# Sheet1.net
KiCad netlist of a schematic drawn in Altium Designer
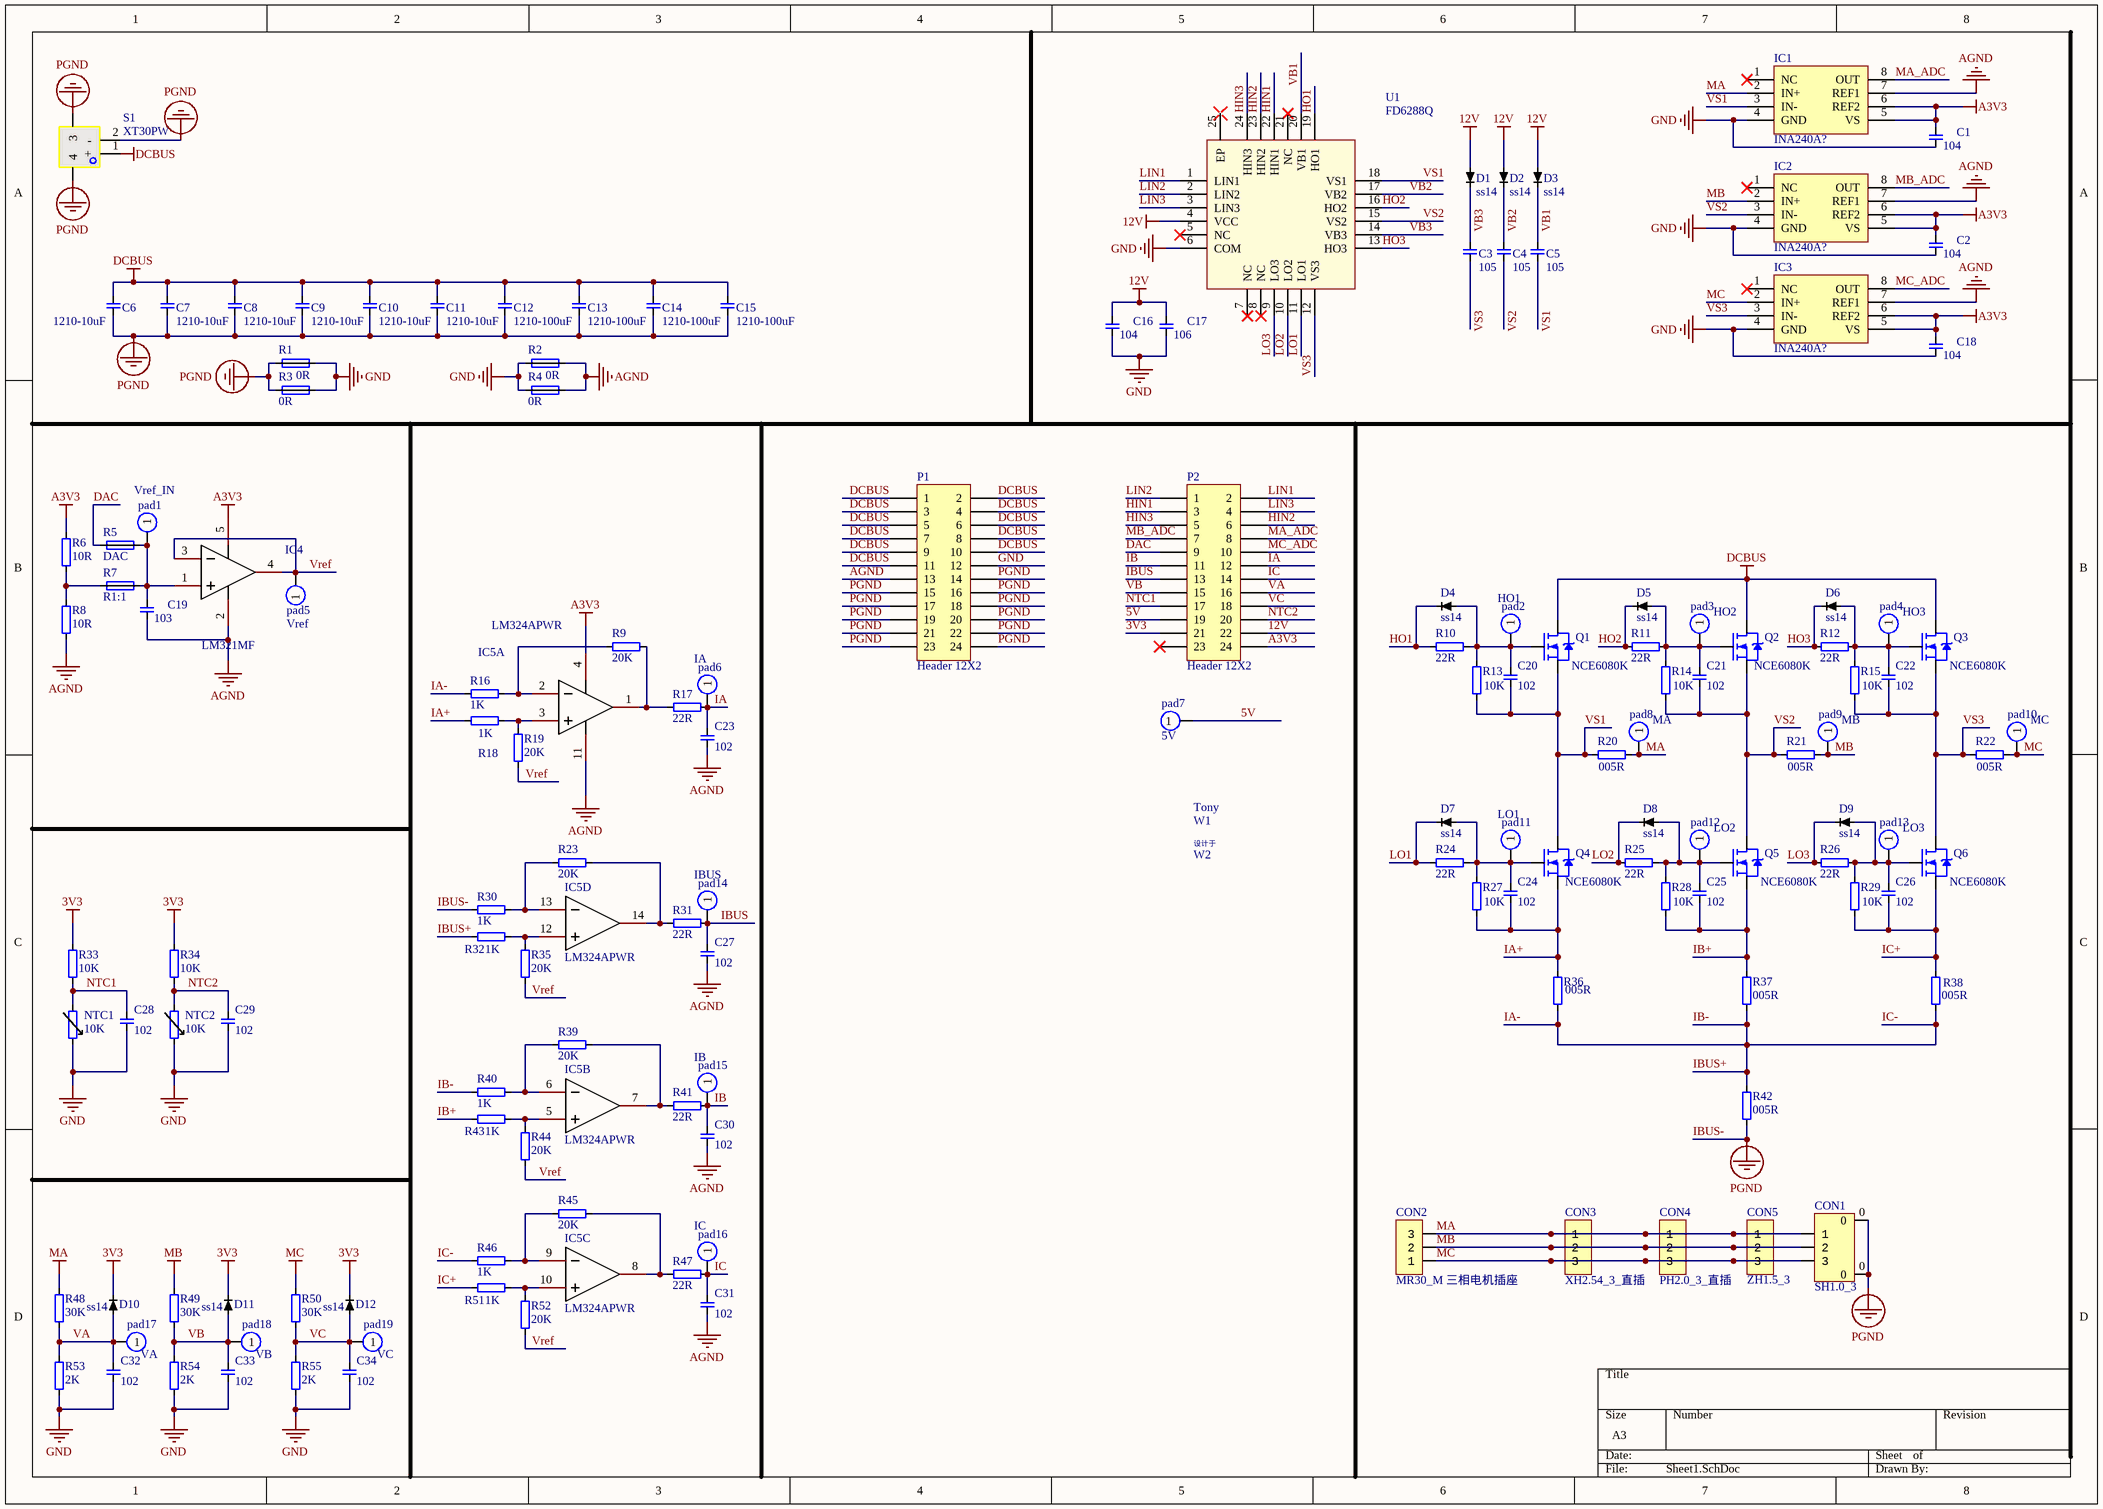
[diagram p0: Sheet1.SchDoc]

(export (version "E")
  (design (tool "Eeschema 10.0.6"))
  (components
    (comp (ref "C1") (value "104") (footprint "CAP_0603") (libsource (lib "基本元件库") (part "cap")))
    (comp (ref "C2") (value "104") (footprint "CAP_0603") (libsource (lib "基本元件库") (part "cap")))
    (comp (ref "C3") (value "105") (footprint "CAP_0603") (libsource (lib "基本元件库") (part "cap")))
    (comp (ref "C4") (value "105") (footprint "CAP_0603") (libsource (lib "基本元件库") (part "cap")))
    (comp (ref "C5") (value "105") (footprint "CAP_0603") (libsource (lib "基本元件库") (part "cap")))
    (comp (ref "C6") (value "1210-10uF") (footprint "CAP_1210_L") (libsource (lib "基本元件库") (part "cap")))
    (comp (ref "C7") (value "1210-10uF") (footprint "CAP_1210_L") (libsource (lib "基本元件库") (part "cap")))
    (comp (ref "C8") (value "1210-10uF") (footprint "CAP_1210_L") (libsource (lib "基本元件库") (part "cap")))
    (comp (ref "C9") (value "1210-10uF") (footprint "CAP_1210_L") (libsource (lib "基本元件库") (part "cap")))
    (comp (ref "C10") (value "1210-10uF") (footprint "CAP_1210_L") (libsource (lib "基本元件库") (part "cap")))
    (comp (ref "C11") (value "1210-10uF") (footprint "CAP_1210_L") (libsource (lib "基本元件库") (part "cap")))
    (comp (ref "C12") (value "1210-100uF") (footprint "CAP_1210_L") (libsource (lib "基本元件库") (part "cap")))
    (comp (ref "C13") (value "1210-100uF") (footprint "CAP_1210_L") (libsource (lib "基本元件库") (part "cap")))
    (comp (ref "C14") (value "1210-100uF") (footprint "CAP_1210_L") (libsource (lib "基本元件库") (part "cap")))
    (comp (ref "C15") (value "1210-100uF") (footprint "CAP_1210_L") (libsource (lib "基本元件库") (part "cap")))
    (comp (ref "C16") (value "104") (footprint "CAP_0603") (libsource (lib "基本元件库") (part "cap")))
    (comp (ref "C17") (value "106") (footprint "CAP_0603") (libsource (lib "基本元件库") (part "cap")))
    (comp (ref "C18") (value "104") (footprint "CAP_0603") (libsource (lib "基本元件库") (part "cap")))
    (comp (ref "C19") (value "103") (footprint "CAP_0603") (libsource (lib "基本元件库") (part "cap")))
    (comp (ref "C20") (value "102") (footprint "CAP_0603") (libsource (lib "基本元件库") (part "cap")))
    (comp (ref "C21") (value "102") (footprint "CAP_0603") (libsource (lib "基本元件库") (part "cap")))
    (comp (ref "C22") (value "102") (footprint "CAP_0603") (libsource (lib "基本元件库") (part "cap")))
    (comp (ref "C23") (value "102") (footprint "CAP_0603") (libsource (lib "基本元件库") (part "cap")))
    (comp (ref "C24") (value "102") (footprint "CAP_0603") (libsource (lib "基本元件库") (part "cap")))
    (comp (ref "C25") (value "102") (footprint "CAP_0603") (libsource (lib "基本元件库") (part "cap")))
    (comp (ref "C26") (value "102") (footprint "CAP_0603") (libsource (lib "基本元件库") (part "cap")))
    (comp (ref "C27") (value "102") (footprint "CAP_0603") (libsource (lib "基本元件库") (part "cap")))
    (comp (ref "C28") (value "102") (footprint "CAP_0603") (libsource (lib "基本元件库") (part "cap")))
    (comp (ref "C29") (value "102") (footprint "CAP_0603") (libsource (lib "基本元件库") (part "cap")))
    (comp (ref "C30") (value "102") (footprint "CAP_0603") (libsource (lib "基本元件库") (part "cap")))
    (comp (ref "C31") (value "102") (footprint "CAP_0603") (libsource (lib "基本元件库") (part "cap")))
    (comp (ref "C32") (value "102") (footprint "CAP_0603") (libsource (lib "基本元件库") (part "cap")))
    (comp (ref "C33") (value "102") (footprint "CAP_0603") (libsource (lib "基本元件库") (part "cap")))
    (comp (ref "C34") (value "102") (footprint "CAP_0603") (libsource (lib "基本元件库") (part "cap")))
    (comp (ref "CON1")
      (value "SH1.0_3")
      (footprint "SH1.0 LS 3P")
      (description "SH1.0 座子")
      (libsource (lib "接插件库") (part "SH1.0_3"))
    )
    (comp (ref "CON2")
      (value "MR30_M 三相电机插座")
      (footprint "MR30-M")
      (description "三相电机线插座")
      (libsource (lib "接插件库") (part "MR30_M"))
    )
    (comp (ref "CON3")
      (value "XH2.54_3_直插")
      (footprint "XH2.54-LI-3P")
      (description "XH2.54_3 直插 座子")
      (libsource (lib "接插件库") (part "XH2.54_3_L"))
    )
    (comp (ref "CON4")
      (value "PH2.0_3_直插")
      (footprint "PH2.0-LI-3P")
      (description "PH2.0_3 直插 座子")
      (libsource (lib "接插件库") (part "PH2.0_3_L"))
    )
    (comp (ref "CON5")
      (value "ZH1.5_3")
      (footprint "ZH1.5-LI-3P")
      (description "ZH1.5_3 座子")
      (libsource (lib "接插件库") (part "ZH1.5_3_L"))
    )
    (comp (ref "D1") (value "ss14") (footprint "SOD-323") (libsource (lib "基本元件库") (part "Diode")))
    (comp (ref "D2") (value "ss14") (footprint "SOD-323") (libsource (lib "基本元件库") (part "Diode")))
    (comp (ref "D3") (value "ss14") (footprint "SOD-323") (libsource (lib "基本元件库") (part "Diode")))
    (comp (ref "D4") (value "ss14") (footprint "SOD-323") (libsource (lib "基本元件库") (part "Diode")))
    (comp (ref "D5") (value "ss14") (footprint "SOD-323") (libsource (lib "基本元件库") (part "Diode")))
    (comp (ref "D6") (value "ss14") (footprint "SOD-323") (libsource (lib "基本元件库") (part "Diode")))
    (comp (ref "D7") (value "ss14") (footprint "SOD-323") (libsource (lib "基本元件库") (part "Diode")))
    (comp (ref "D8") (value "ss14") (footprint "SOD-323") (libsource (lib "基本元件库") (part "Diode")))
    (comp (ref "D9") (value "ss14") (footprint "SOD-323") (libsource (lib "基本元件库") (part "Diode")))
    (comp (ref "D10") (value "ss14") (footprint "SOD-323") (libsource (lib "基本元件库") (part "Diode")))
    (comp (ref "D11") (value "ss14") (footprint "SOD-323") (libsource (lib "基本元件库") (part "Diode")))
    (comp (ref "D12") (value "ss14") (footprint "SOD-323") (libsource (lib "基本元件库") (part "Diode")))
    (comp (ref "IC1")
      (value "INA240A?")
      (footprint "TSSOP8")
      (description "电流采样芯片\r\nA1=20 A2=50 A3=100 A4=200")
      (libsource (lib "IC") (part "INA240"))
    )
    (comp (ref "IC2")
      (value "INA240A?")
      (footprint "TSSOP8")
      (description "电流采样芯片\r\nA1=20 A2=50 A3=100 A4=200")
      (libsource (lib "IC") (part "INA240"))
    )
    (comp (ref "IC3")
      (value "INA240A?")
      (footprint "TSSOP8")
      (description "电流采样芯片\r\nA1=20 A2=50 A3=100 A4=200")
      (libsource (lib "IC") (part "INA240"))
    )
    (comp (ref "IC4")
      (value "LM321MF")
      (footprint "SOT23-5")
      (description "单通道运放")
      (fields (field (name "MANUFACTURER") "TI(德州仪器)") (field (name "MANUFACTURER PART") "LM321MF/NOPB"))
      (libsource (lib "IC") (part "LM321MF"))
    )
    (comp (ref "IC5")
      (value "LM324APWR")
      (footprint "SOP14")
      (description "四通道运放")
      (fields
        (field (name "MANUFACTURER") "TL084CPWR")
        (field (name "MANUFACTURER PART") "TI")
        (field (name "NAME") "LM324APWR")
      )
      (libsource (lib "IC") (part "LM324APWR"))
    )
    (comp (ref "NTC1")
      (value "10K")
      (footprint "RES_0603")
      (description "温敏电阻")
      (libsource (lib "基本元件库") (part "NTC"))
    )
    (comp (ref "NTC2")
      (value "10K")
      (footprint "RES_0603")
      (description "温敏电阻")
      (libsource (lib "基本元件库") (part "NTC"))
    )
    (comp (ref "P1")
      (value "Header 12X2")
      (footprint "HDR2X12")
      (description "Header, 12-Pin, Dual row")
      (fields (field (name "PUBLISHER") "Altium Limited"))
      (libsource (lib "Miscellaneous Connectors") (part "Header 12X2"))
    )
    (comp (ref "P2")
      (value "Header 12X2")
      (footprint "HDR2X12")
      (description "Header, 12-Pin, Dual row")
      (fields (field (name "PUBLISHER") "Altium Limited"))
      (libsource (lib "Miscellaneous Connectors") (part "Header 12X2"))
    )
    (comp (ref "pad1")
      (value "Vref_IN")
      (footprint "PAD-1")
      (description "50mil单点焊盘，用于测试")
      (libsource (lib "基本元件库") (part "PAD"))
    )
    (comp (ref "pad2")
      (value "HO1")
      (footprint "PAD-1")
      (description "50mil单点焊盘，用于测试")
      (libsource (lib "基本元件库") (part "PAD"))
    )
    (comp (ref "pad3")
      (value "HO2")
      (footprint "PAD-1")
      (description "50mil单点焊盘，用于测试")
      (libsource (lib "基本元件库") (part "PAD"))
    )
    (comp (ref "pad4")
      (value "HO3")
      (footprint "PAD-1")
      (description "50mil单点焊盘，用于测试")
      (libsource (lib "基本元件库") (part "PAD"))
    )
    (comp (ref "pad5")
      (value "Vref")
      (footprint "PAD-1")
      (description "50mil单点焊盘，用于测试")
      (libsource (lib "基本元件库") (part "PAD"))
    )
    (comp (ref "pad6")
      (value "IA")
      (footprint "PAD-1")
      (description "50mil单点焊盘，用于测试")
      (libsource (lib "基本元件库") (part "PAD"))
    )
    (comp (ref "pad7")
      (value "5V")
      (footprint "PAD-1")
      (description "50mil单点焊盘，用于测试")
      (libsource (lib "基本元件库") (part "PAD"))
    )
    (comp (ref "pad8")
      (value "MA")
      (footprint "PAD-1")
      (description "50mil单点焊盘，用于测试")
      (libsource (lib "基本元件库") (part "PAD"))
    )
    (comp (ref "pad9")
      (value "MB")
      (footprint "PAD-1")
      (description "50mil单点焊盘，用于测试")
      (libsource (lib "基本元件库") (part "PAD"))
    )
    (comp (ref "pad10")
      (value "MC")
      (footprint "PAD-1")
      (description "50mil单点焊盘，用于测试")
      (libsource (lib "基本元件库") (part "PAD"))
    )
    (comp (ref "pad11")
      (value "LO1")
      (footprint "PAD-1")
      (description "50mil单点焊盘，用于测试")
      (libsource (lib "基本元件库") (part "PAD"))
    )
    (comp (ref "pad12")
      (value "LO2")
      (footprint "PAD-1")
      (description "50mil单点焊盘，用于测试")
      (libsource (lib "基本元件库") (part "PAD"))
    )
    (comp (ref "pad13")
      (value "LO3")
      (footprint "PAD-1")
      (description "50mil单点焊盘，用于测试")
      (libsource (lib "基本元件库") (part "PAD"))
    )
    (comp (ref "pad14")
      (value "IBUS")
      (footprint "PAD-1")
      (description "50mil单点焊盘，用于测试")
      (libsource (lib "基本元件库") (part "PAD"))
    )
    (comp (ref "pad15")
      (value "IB")
      (footprint "PAD-1")
      (description "50mil单点焊盘，用于测试")
      (libsource (lib "基本元件库") (part "PAD"))
    )
    (comp (ref "pad16")
      (value "IC")
      (footprint "PAD-1")
      (description "50mil单点焊盘，用于测试")
      (libsource (lib "基本元件库") (part "PAD"))
    )
    (comp (ref "pad17")
      (value "VA")
      (footprint "PAD-1")
      (description "50mil单点焊盘，用于测试")
      (libsource (lib "基本元件库") (part "PAD"))
    )
    (comp (ref "pad18")
      (value "VB")
      (footprint "PAD-1")
      (description "50mil单点焊盘，用于测试")
      (libsource (lib "基本元件库") (part "PAD"))
    )
    (comp (ref "pad19")
      (value "VC")
      (footprint "PAD-1")
      (description "50mil单点焊盘，用于测试")
      (libsource (lib "基本元件库") (part "PAD"))
    )
    (comp (ref "Q1")
      (value "NCE6080K")
      (footprint "TO252-2")
      (description "N沟道MOSFIT\r\n-NCE6080K-TO252-2")
      (libsource (lib "基本元件库") (part "NMOS"))
    )
    (comp (ref "Q2")
      (value "NCE6080K")
      (footprint "TO252-2")
      (description "N沟道MOSFIT\r\n-NCE6080K-TO252-2")
      (libsource (lib "基本元件库") (part "NMOS"))
    )
    (comp (ref "Q3")
      (value "NCE6080K")
      (footprint "TO252-2")
      (description "N沟道MOSFIT\r\n-NCE6080K-TO252-2")
      (libsource (lib "基本元件库") (part "NMOS"))
    )
    (comp (ref "Q4")
      (value "NCE6080K")
      (footprint "TO252-2")
      (description "N沟道MOSFIT\r\n-NCE6080K-TO252-2")
      (libsource (lib "基本元件库") (part "NMOS"))
    )
    (comp (ref "Q5")
      (value "NCE6080K")
      (footprint "TO252-2")
      (description "N沟道MOSFIT\r\n-NCE6080K-TO252-2")
      (libsource (lib "基本元件库") (part "NMOS"))
    )
    (comp (ref "Q6")
      (value "NCE6080K")
      (footprint "TO252-2")
      (description "N沟道MOSFIT\r\n-NCE6080K-TO252-2")
      (libsource (lib "基本元件库") (part "NMOS"))
    )
    (comp (ref "R1") (value "0R") (footprint "RES_0805-SHORT") (libsource (lib "基本元件库") (part "Res-SHORT")))
    (comp (ref "R2") (value "0R") (footprint "RES_0805-SHORT") (libsource (lib "基本元件库") (part "Res-SHORT")))
    (comp (ref "R3") (value "0R") (footprint "RES_0805-SHORT") (libsource (lib "基本元件库") (part "Res-SHORT")))
    (comp (ref "R4") (value "0R") (footprint "RES_0805-SHORT") (libsource (lib "基本元件库") (part "Res-SHORT")))
    (comp (ref "R5") (value "DAC") (footprint "RES_0603-SHORT") (libsource (lib "基本元件库") (part "Res-SHORT")))
    (comp (ref "R6") (value "10R") (footprint "RES_0603") (libsource (lib "基本元件库") (part "Res")))
    (comp (ref "R7") (value "R1:1") (footprint "RES_0603-SHORT") (libsource (lib "基本元件库") (part "Res-SHORT")))
    (comp (ref "R8") (value "10R") (footprint "RES_0603") (libsource (lib "基本元件库") (part "Res")))
    (comp (ref "R9") (value "20K") (footprint "RES_0603") (libsource (lib "基本元件库") (part "Res")))
    (comp (ref "R10") (value "22R") (footprint "RES_0603") (libsource (lib "基本元件库") (part "Res")))
    (comp (ref "R11") (value "22R") (footprint "RES_0603") (libsource (lib "基本元件库") (part "Res")))
    (comp (ref "R12") (value "22R") (footprint "RES_0603") (libsource (lib "基本元件库") (part "Res")))
    (comp (ref "R13") (value "10K") (footprint "RES_0603") (libsource (lib "基本元件库") (part "Res")))
    (comp (ref "R14") (value "10K") (footprint "RES_0603") (libsource (lib "基本元件库") (part "Res")))
    (comp (ref "R15") (value "10K") (footprint "RES_0603") (libsource (lib "基本元件库") (part "Res")))
    (comp (ref "R16") (value "1K") (footprint "RES_0603") (libsource (lib "基本元件库") (part "Res")))
    (comp (ref "R17") (value "22R") (footprint "RES_0603") (libsource (lib "基本元件库") (part "Res")))
    (comp (ref "R18") (value "1K") (footprint "RES_0603") (libsource (lib "基本元件库") (part "Res")))
    (comp (ref "R19") (value "20K") (footprint "RES_0603") (libsource (lib "基本元件库") (part "Res")))
    (comp (ref "R20") (value "005R") (footprint "RES_2512") (libsource (lib "基本元件库") (part "Res")))
    (comp (ref "R21") (value "005R") (footprint "RES_2512") (libsource (lib "基本元件库") (part "Res")))
    (comp (ref "R22") (value "005R") (footprint "RES_2512") (libsource (lib "基本元件库") (part "Res")))
    (comp (ref "R23") (value "20K") (footprint "RES_0603") (libsource (lib "基本元件库") (part "Res")))
    (comp (ref "R24") (value "22R") (footprint "RES_0603") (libsource (lib "基本元件库") (part "Res")))
    (comp (ref "R25") (value "22R") (footprint "RES_0603") (libsource (lib "基本元件库") (part "Res")))
    (comp (ref "R26") (value "22R") (footprint "RES_0603") (libsource (lib "基本元件库") (part "Res")))
    (comp (ref "R27") (value "10K") (footprint "RES_0603") (libsource (lib "基本元件库") (part "Res")))
    (comp (ref "R28") (value "10K") (footprint "RES_0603") (libsource (lib "基本元件库") (part "Res")))
    (comp (ref "R29") (value "10K") (footprint "RES_0603") (libsource (lib "基本元件库") (part "Res")))
    (comp (ref "R30") (value "1K") (footprint "RES_0603") (libsource (lib "基本元件库") (part "Res")))
    (comp (ref "R31") (value "22R") (footprint "RES_0603") (libsource (lib "基本元件库") (part "Res")))
    (comp (ref "R32") (value "1K") (footprint "RES_0603") (libsource (lib "基本元件库") (part "Res")))
    (comp (ref "R33") (value "10K") (footprint "RES_0603") (libsource (lib "基本元件库") (part "Res")))
    (comp (ref "R34") (value "10K") (footprint "RES_0603") (libsource (lib "基本元件库") (part "Res")))
    (comp (ref "R35") (value "20K") (footprint "RES_0603") (libsource (lib "基本元件库") (part "Res")))
    (comp (ref "R36") (value "005R") (footprint "RES_2512") (libsource (lib "基本元件库") (part "Res")))
    (comp (ref "R37") (value "005R") (footprint "RES_2512") (libsource (lib "基本元件库") (part "Res")))
    (comp (ref "R38") (value "005R") (footprint "RES_2512") (libsource (lib "基本元件库") (part "Res")))
    (comp (ref "R39") (value "20K") (footprint "RES_0603") (libsource (lib "基本元件库") (part "Res")))
    (comp (ref "R40") (value "1K") (footprint "RES_0603") (libsource (lib "基本元件库") (part "Res")))
    (comp (ref "R41") (value "22R") (footprint "RES_0603") (libsource (lib "基本元件库") (part "Res")))
    (comp (ref "R42") (value "005R") (footprint "RES_2512") (libsource (lib "基本元件库") (part "Res")))
    (comp (ref "R43") (value "1K") (footprint "RES_0603") (libsource (lib "基本元件库") (part "Res")))
    (comp (ref "R44") (value "20K") (footprint "RES_0603") (libsource (lib "基本元件库") (part "Res")))
    (comp (ref "R45") (value "20K") (footprint "RES_0603") (libsource (lib "基本元件库") (part "Res")))
    (comp (ref "R46") (value "1K") (footprint "RES_0603") (libsource (lib "基本元件库") (part "Res")))
    (comp (ref "R47") (value "22R") (footprint "RES_0603") (libsource (lib "基本元件库") (part "Res")))
    (comp (ref "R48") (value "30K") (footprint "RES_0603") (libsource (lib "基本元件库") (part "Res")))
    (comp (ref "R49") (value "30K") (footprint "RES_0603") (libsource (lib "基本元件库") (part "Res")))
    (comp (ref "R50") (value "30K") (footprint "RES_0603") (libsource (lib "基本元件库") (part "Res")))
    (comp (ref "R51") (value "1K") (footprint "RES_0603") (libsource (lib "基本元件库") (part "Res")))
    (comp (ref "R52") (value "20K") (footprint "RES_0603") (libsource (lib "基本元件库") (part "Res")))
    (comp (ref "R53") (value "2K") (footprint "RES_0603") (libsource (lib "基本元件库") (part "Res")))
    (comp (ref "R54") (value "2K") (footprint "RES_0603") (libsource (lib "基本元件库") (part "Res")))
    (comp (ref "R55") (value "2K") (footprint "RES_0603") (libsource (lib "基本元件库") (part "Res")))
    (comp (ref "S1")
      (value "XT30PW")
      (footprint "XT30PW-M")
      (description "XT30PW-I/O")
      (libsource (lib "SOURCE") (part "XT30PW"))
    )
    (comp (ref "U1")
      (value "FD6288Q")
      (footprint "QFN-24_4X4")
      (description "栅极驱动IC")
      (libsource (lib "IC") (part "FD6288Q"))
    )
    (comp (ref "W1") (value "Tony") (footprint "Tony_2(200-70)") (libsource (lib "丝印库") (part "Tony")))
    (comp (ref "W2") (value "设计于") (footprint "designed by（430-70）") (libsource (lib "丝印库") (part "设计于")))
  )
  (nets
    (net (code "1") (name "/5V") (class "Default")
      (node (ref "P2") (pin "19") (pinfunction "19_19") (pintype "passive"))
      (node (ref "pad7") (pin "1") (pinfunction "1_1") (pintype "passive"))
    )
    (net (code "2") (name "/DAC") (class "Default")
      (node (ref "P2") (pin "9") (pinfunction "9_9") (pintype "passive"))
      (node (ref "R5") (pin "1") (pinfunction "1_1") (pintype "passive"))
    )
    (net (code "3") (name "/HIN1") (class "Default")
      (node (ref "P2") (pin "3") (pinfunction "3_3") (pintype "passive"))
      (node (ref "U1") (pin "22") (pinfunction "HIN1_22") (pintype "passive"))
    )
    (net (code "4") (name "/HIN2") (class "Default")
      (node (ref "P2") (pin "6") (pinfunction "6_6") (pintype "passive"))
      (node (ref "U1") (pin "23") (pinfunction "HIN2_23") (pintype "passive"))
    )
    (net (code "5") (name "/HIN3") (class "Default")
      (node (ref "P2") (pin "5") (pinfunction "5_5") (pintype "passive"))
      (node (ref "U1") (pin "24") (pinfunction "HIN3_24") (pintype "passive"))
    )
    (net (code "6") (name "/HO1") (class "Default")
      (node (ref "D4") (pin "2") (pintype "passive"))
      (node (ref "R10") (pin "2") (pinfunction "2_2") (pintype "passive"))
      (node (ref "U1") (pin "19") (pinfunction "HO1_19") (pintype "passive"))
    )
    (net (code "7") (name "/HO2") (class "Default")
      (node (ref "D5") (pin "2") (pintype "passive"))
      (node (ref "R11") (pin "2") (pinfunction "2_2") (pintype "passive"))
      (node (ref "U1") (pin "16") (pinfunction "HO2_16") (pintype "passive"))
    )
    (net (code "8") (name "/HO3") (class "Default")
      (node (ref "D6") (pin "2") (pintype "passive"))
      (node (ref "R12") (pin "2") (pinfunction "2_2") (pintype "passive"))
      (node (ref "U1") (pin "13") (pinfunction "HO3_13") (pintype "passive"))
    )
    (net (code "9") (name "/IA") (class "Default")
      (node (ref "C23") (pin "2") (pinfunction "2_2") (pintype "passive"))
      (node (ref "P2") (pin "12") (pinfunction "12_12") (pintype "passive"))
      (node (ref "R17") (pin "2") (pinfunction "2_2") (pintype "passive"))
      (node (ref "pad6") (pin "1") (pinfunction "1_1") (pintype "passive"))
    )
    (net (code "10") (name "/IA+") (class "Default")
      (node (ref "C24") (pin "1") (pinfunction "1_1") (pintype "passive"))
      (node (ref "Q4") (pin "3") (pinfunction "S_3") (pintype "passive"))
      (node (ref "R18") (pin "1") (pinfunction "1_1") (pintype "passive"))
      (node (ref "R27") (pin "2") (pinfunction "2_2") (pintype "passive"))
      (node (ref "R36") (pin "2") (pinfunction "2_2") (pintype "passive"))
    )
    (net (code "11") (name "/IA-") (class "Default")
      (node (ref "R16") (pin "1") (pinfunction "1_1") (pintype "passive"))
      (node (ref "R32") (pin "1") (pinfunction "1_1") (pintype "passive"))
      (node (ref "R36") (pin "1") (pinfunction "1_1") (pintype "passive"))
      (node (ref "R37") (pin "1") (pinfunction "1_1") (pintype "passive"))
      (node (ref "R38") (pin "1") (pinfunction "1_1") (pintype "passive"))
      (node (ref "R40") (pin "1") (pinfunction "1_1") (pintype "passive"))
      (node (ref "R42") (pin "2") (pinfunction "2_2") (pintype "passive"))
      (node (ref "R46") (pin "1") (pinfunction "1_1") (pintype "passive"))
    )
    (net (code "12") (name "/IB") (class "Default")
      (node (ref "C30") (pin "2") (pinfunction "2_2") (pintype "passive"))
      (node (ref "P2") (pin "11") (pinfunction "11_11") (pintype "passive"))
      (node (ref "R41") (pin "2") (pinfunction "2_2") (pintype "passive"))
      (node (ref "pad15") (pin "1") (pinfunction "1_1") (pintype "passive"))
    )
    (net (code "13") (name "/IB+") (class "Default")
      (node (ref "C25") (pin "1") (pinfunction "1_1") (pintype "passive"))
      (node (ref "Q5") (pin "3") (pinfunction "S_3") (pintype "passive"))
      (node (ref "R28") (pin "2") (pinfunction "2_2") (pintype "passive"))
      (node (ref "R37") (pin "2") (pinfunction "2_2") (pintype "passive"))
      (node (ref "R43") (pin "1") (pinfunction "1_1") (pintype "passive"))
    )
    (net (code "14") (name "/IBUS") (class "Default")
      (node (ref "C27") (pin "2") (pinfunction "2_2") (pintype "passive"))
      (node (ref "P2") (pin "13") (pinfunction "13_13") (pintype "passive"))
      (node (ref "R31") (pin "2") (pinfunction "2_2") (pintype "passive"))
      (node (ref "pad14") (pin "1") (pinfunction "1_1") (pintype "passive"))
    )
    (net (code "15") (name "/IC") (class "Default")
      (node (ref "C31") (pin "2") (pinfunction "2_2") (pintype "passive"))
      (node (ref "P2") (pin "14") (pinfunction "14_14") (pintype "passive"))
      (node (ref "R47") (pin "2") (pinfunction "2_2") (pintype "passive"))
      (node (ref "pad16") (pin "1") (pinfunction "1_1") (pintype "passive"))
    )
    (net (code "16") (name "/IC+") (class "Default")
      (node (ref "C26") (pin "1") (pinfunction "1_1") (pintype "passive"))
      (node (ref "Q6") (pin "3") (pinfunction "S_3") (pintype "passive"))
      (node (ref "R29") (pin "2") (pinfunction "2_2") (pintype "passive"))
      (node (ref "R38") (pin "2") (pinfunction "2_2") (pintype "passive"))
      (node (ref "R51") (pin "1") (pinfunction "1_1") (pintype "passive"))
    )
    (net (code "17") (name "/LIN1") (class "Default")
      (node (ref "P2") (pin "2") (pinfunction "2_2") (pintype "passive"))
      (node (ref "U1") (pin "1") (pinfunction "LIN1_1") (pintype "passive"))
    )
    (net (code "18") (name "/LIN2") (class "Default")
      (node (ref "P2") (pin "1") (pinfunction "1_1") (pintype "passive"))
      (node (ref "U1") (pin "2") (pinfunction "LIN2_2") (pintype "passive"))
    )
    (net (code "19") (name "/LIN3") (class "Default")
      (node (ref "P2") (pin "4") (pinfunction "4_4") (pintype "passive"))
      (node (ref "U1") (pin "3") (pinfunction "LIN3_3") (pintype "passive"))
    )
    (net (code "20") (name "/LO1") (class "Default")
      (node (ref "D7") (pin "2") (pintype "passive"))
      (node (ref "R24") (pin "2") (pinfunction "2_2") (pintype "passive"))
      (node (ref "U1") (pin "11") (pinfunction "LO1_11") (pintype "passive"))
    )
    (net (code "21") (name "/LO2") (class "Default")
      (node (ref "D8") (pin "2") (pintype "passive"))
      (node (ref "R25") (pin "2") (pinfunction "2_2") (pintype "passive"))
      (node (ref "U1") (pin "10") (pinfunction "LO2_10") (pintype "passive"))
    )
    (net (code "22") (name "/LO3") (class "Default")
      (node (ref "D9") (pin "2") (pintype "passive"))
      (node (ref "R26") (pin "2") (pinfunction "2_2") (pintype "passive"))
      (node (ref "U1") (pin "9") (pinfunction "LO3_9") (pintype "passive"))
    )
    (net (code "23") (name "/MA_ADC") (class "Default")
      (node (ref "IC1") (pin "8") (pinfunction "OUT_8") (pintype "passive"))
      (node (ref "P2") (pin "8") (pinfunction "8_8") (pintype "passive"))
    )
    (net (code "24") (name "/MB_ADC") (class "Default")
      (node (ref "IC2") (pin "8") (pinfunction "OUT_8") (pintype "passive"))
      (node (ref "P2") (pin "7") (pinfunction "7_7") (pintype "passive"))
    )
    (net (code "25") (name "/MC_ADC") (class "Default")
      (node (ref "IC3") (pin "8") (pinfunction "OUT_8") (pintype "passive"))
      (node (ref "P2") (pin "10") (pinfunction "10_10") (pintype "passive"))
    )
    (net (code "26") (name "/NTC1") (class "Default")
      (node (ref "C28") (pin "2") (pinfunction "2_2") (pintype "passive"))
      (node (ref "NTC1") (pin "1") (pinfunction "1_1") (pintype "passive"))
      (node (ref "P2") (pin "17") (pinfunction "17_17") (pintype "passive"))
      (node (ref "R33") (pin "2") (pinfunction "2_2") (pintype "passive"))
    )
    (net (code "27") (name "/NTC2") (class "Default")
      (node (ref "C29") (pin "2") (pinfunction "2_2") (pintype "passive"))
      (node (ref "NTC2") (pin "1") (pinfunction "1_1") (pintype "passive"))
      (node (ref "P2") (pin "20") (pinfunction "20_20") (pintype "passive"))
      (node (ref "R34") (pin "2") (pinfunction "2_2") (pintype "passive"))
    )
    (net (code "28") (name "/VA") (class "Default")
      (node (ref "C32") (pin "2") (pinfunction "2_2") (pintype "passive"))
      (node (ref "D10") (pin "1") (pintype "passive"))
      (node (ref "P2") (pin "16") (pinfunction "16_16") (pintype "passive"))
      (node (ref "R48") (pin "2") (pinfunction "2_2") (pintype "passive"))
      (node (ref "R53") (pin "1") (pinfunction "1_1") (pintype "passive"))
      (node (ref "pad17") (pin "1") (pinfunction "1_1") (pintype "passive"))
    )
    (net (code "29") (name "/VB") (class "Default")
      (node (ref "C33") (pin "2") (pinfunction "2_2") (pintype "passive"))
      (node (ref "D11") (pin "1") (pintype "passive"))
      (node (ref "P2") (pin "15") (pinfunction "15_15") (pintype "passive"))
      (node (ref "R49") (pin "2") (pinfunction "2_2") (pintype "passive"))
      (node (ref "R54") (pin "1") (pinfunction "1_1") (pintype "passive"))
      (node (ref "pad18") (pin "1") (pinfunction "1_1") (pintype "passive"))
    )
    (net (code "30") (name "/VB1") (class "Default")
      (node (ref "C5") (pin "2") (pinfunction "2_2") (pintype "passive"))
      (node (ref "D3") (pin "2") (pintype "passive"))
      (node (ref "U1") (pin "20") (pinfunction "VB1_20") (pintype "passive"))
    )
    (net (code "31") (name "/VB2") (class "Default")
      (node (ref "C4") (pin "2") (pinfunction "2_2") (pintype "passive"))
      (node (ref "D2") (pin "2") (pintype "passive"))
      (node (ref "U1") (pin "17") (pinfunction "VB2_17") (pintype "passive"))
    )
    (net (code "32") (name "/VB3") (class "Default")
      (node (ref "C3") (pin "2") (pinfunction "2_2") (pintype "passive"))
      (node (ref "D1") (pin "2") (pintype "passive"))
      (node (ref "U1") (pin "14") (pinfunction "VB3_14") (pintype "passive"))
    )
    (net (code "33") (name "/VC") (class "Default")
      (node (ref "C34") (pin "2") (pinfunction "2_2") (pintype "passive"))
      (node (ref "D12") (pin "1") (pintype "passive"))
      (node (ref "P2") (pin "18") (pinfunction "18_18") (pintype "passive"))
      (node (ref "R50") (pin "2") (pinfunction "2_2") (pintype "passive"))
      (node (ref "R55") (pin "1") (pinfunction "1_1") (pintype "passive"))
      (node (ref "pad19") (pin "1") (pinfunction "1_1") (pintype "passive"))
    )
    (net (code "34") (name "/VS1") (class "Default")
      (node (ref "C20") (pin "1") (pinfunction "1_1") (pintype "passive"))
      (node (ref "C5") (pin "1") (pinfunction "1_1") (pintype "passive"))
      (node (ref "IC1") (pin "3") (pinfunction "IN-_3") (pintype "passive"))
      (node (ref "Q1") (pin "3") (pinfunction "S_3") (pintype "passive"))
      (node (ref "Q4") (pin "2") (pinfunction "D_2") (pintype "passive"))
      (node (ref "R13") (pin "2") (pinfunction "2_2") (pintype "passive"))
      (node (ref "R20") (pin "1") (pinfunction "1_1") (pintype "passive"))
      (node (ref "U1") (pin "18") (pinfunction "VS1_18") (pintype "passive"))
    )
    (net (code "35") (name "/VS2") (class "Default")
      (node (ref "C21") (pin "1") (pinfunction "1_1") (pintype "passive"))
      (node (ref "C4") (pin "1") (pinfunction "1_1") (pintype "passive"))
      (node (ref "IC2") (pin "3") (pinfunction "IN-_3") (pintype "passive"))
      (node (ref "Q2") (pin "3") (pinfunction "S_3") (pintype "passive"))
      (node (ref "Q5") (pin "2") (pinfunction "D_2") (pintype "passive"))
      (node (ref "R14") (pin "2") (pinfunction "2_2") (pintype "passive"))
      (node (ref "R21") (pin "1") (pinfunction "1_1") (pintype "passive"))
      (node (ref "U1") (pin "15") (pinfunction "VS2_15") (pintype "passive"))
    )
    (net (code "36") (name "/VS3") (class "Default")
      (node (ref "C22") (pin "1") (pinfunction "1_1") (pintype "passive"))
      (node (ref "C3") (pin "1") (pinfunction "1_1") (pintype "passive"))
      (node (ref "IC3") (pin "3") (pinfunction "IN-_3") (pintype "passive"))
      (node (ref "Q3") (pin "3") (pinfunction "S_3") (pintype "passive"))
      (node (ref "Q6") (pin "2") (pinfunction "D_2") (pintype "passive"))
      (node (ref "R15") (pin "2") (pinfunction "2_2") (pintype "passive"))
      (node (ref "R22") (pin "1") (pinfunction "1_1") (pintype "passive"))
      (node (ref "U1") (pin "12") (pinfunction "VS3_12") (pintype "passive"))
    )
    (net (code "37") (name "/Vref") (class "Default")
      (node (ref "IC4") (pin "3") (pinfunction "IN-_3") (pintype "passive"))
      (node (ref "IC4") (pin "4") (pinfunction "OUT_4") (pintype "passive"))
      (node (ref "R19") (pin "1") (pinfunction "1_1") (pintype "passive"))
      (node (ref "R35") (pin "1") (pinfunction "1_1") (pintype "passive"))
      (node (ref "R44") (pin "1") (pinfunction "1_1") (pintype "passive"))
      (node (ref "R52") (pin "1") (pinfunction "1_1") (pintype "passive"))
      (node (ref "pad5") (pin "1") (pinfunction "1_1") (pintype "passive"))
    )
    (net (code "38") (name "3V3") (class "Default")
      (node (ref "D10") (pin "2") (pintype "passive"))
      (node (ref "D11") (pin "2") (pintype "passive"))
      (node (ref "D12") (pin "2") (pintype "passive"))
      (node (ref "P2") (pin "21") (pinfunction "21_21") (pintype "passive"))
      (node (ref "R33") (pin "1") (pinfunction "1_1") (pintype "passive"))
      (node (ref "R34") (pin "1") (pinfunction "1_1") (pintype "passive"))
    )
    (net (code "39") (name "12V") (class "Default")
      (node (ref "C16") (pin "2") (pinfunction "2_2") (pintype "passive"))
      (node (ref "C17") (pin "2") (pinfunction "2_2") (pintype "passive"))
      (node (ref "D1") (pin "1") (pintype "passive"))
      (node (ref "D2") (pin "1") (pintype "passive"))
      (node (ref "D3") (pin "1") (pintype "passive"))
      (node (ref "P2") (pin "22") (pinfunction "22_22") (pintype "passive"))
      (node (ref "U1") (pin "4") (pinfunction "VCC_4") (pintype "passive"))
    )
    (net (code "40") (name "A3V3") (class "Default")
      (node (ref "C1") (pin "2") (pinfunction "2_2") (pintype "passive"))
      (node (ref "C18") (pin "2") (pinfunction "2_2") (pintype "passive"))
      (node (ref "C2") (pin "2") (pinfunction "2_2") (pintype "passive"))
      (node (ref "IC1") (pin "5") (pinfunction "VS_5") (pintype "passive"))
      (node (ref "IC1") (pin "6") (pinfunction "REF2_6") (pintype "passive"))
      (node (ref "IC2") (pin "5") (pinfunction "VS_5") (pintype "passive"))
      (node (ref "IC2") (pin "6") (pinfunction "REF2_6") (pintype "passive"))
      (node (ref "IC3") (pin "5") (pinfunction "VS_5") (pintype "passive"))
      (node (ref "IC3") (pin "6") (pinfunction "REF2_6") (pintype "passive"))
      (node (ref "IC4") (pin "5") (pinfunction "V+_5") (pintype "passive"))
      (node (ref "IC5") (pin "4") (pinfunction "VCC+_4") (pintype "passive"))
      (node (ref "P2") (pin "24") (pinfunction "24_24") (pintype "passive"))
      (node (ref "R6") (pin "1") (pinfunction "1_1") (pintype "passive"))
    )
    (net (code "41") (name "AGND") (class "Default")
      (node (ref "C19") (pin "1") (pinfunction "1_1") (pintype "passive"))
      (node (ref "C23") (pin "1") (pinfunction "1_1") (pintype "passive"))
      (node (ref "C27") (pin "1") (pinfunction "1_1") (pintype "passive"))
      (node (ref "C30") (pin "1") (pinfunction "1_1") (pintype "passive"))
      (node (ref "C31") (pin "1") (pinfunction "1_1") (pintype "passive"))
      (node (ref "IC1") (pin "7") (pinfunction "REF1_7") (pintype "passive"))
      (node (ref "IC2") (pin "7") (pinfunction "REF1_7") (pintype "passive"))
      (node (ref "IC3") (pin "7") (pinfunction "REF1_7") (pintype "passive"))
      (node (ref "IC4") (pin "2") (pinfunction "V-_2") (pintype "passive"))
      (node (ref "IC5") (pin "11") (pinfunction "VCC-_11") (pintype "passive"))
      (node (ref "P1") (pin "13") (pinfunction "13_13") (pintype "passive"))
      (node (ref "R2") (pin "2") (pinfunction "2_2") (pintype "passive"))
      (node (ref "R4") (pin "2") (pinfunction "2_2") (pintype "passive"))
      (node (ref "R8") (pin "2") (pinfunction "2_2") (pintype "passive"))
    )
    (net (code "42") (name "DCBUS") (class "Default")
      (node (ref "C10") (pin "2") (pinfunction "2_2") (pintype "passive"))
      (node (ref "C11") (pin "2") (pinfunction "2_2") (pintype "passive"))
      (node (ref "C12") (pin "2") (pinfunction "2_2") (pintype "passive"))
      (node (ref "C13") (pin "2") (pinfunction "2_2") (pintype "passive"))
      (node (ref "C14") (pin "2") (pinfunction "2_2") (pintype "passive"))
      (node (ref "C15") (pin "2") (pinfunction "2_2") (pintype "passive"))
      (node (ref "C6") (pin "2") (pinfunction "2_2") (pintype "passive"))
      (node (ref "C7") (pin "2") (pinfunction "2_2") (pintype "passive"))
      (node (ref "C8") (pin "2") (pinfunction "2_2") (pintype "passive"))
      (node (ref "C9") (pin "2") (pinfunction "2_2") (pintype "passive"))
      (node (ref "P1") (pin "1") (pinfunction "1_1") (pintype "passive"))
      (node (ref "P1") (pin "10") (pinfunction "10_10") (pintype "passive"))
      (node (ref "P1") (pin "11") (pinfunction "11_11") (pintype "passive"))
      (node (ref "P1") (pin "2") (pinfunction "2_2") (pintype "passive"))
      (node (ref "P1") (pin "3") (pinfunction "3_3") (pintype "passive"))
      (node (ref "P1") (pin "4") (pinfunction "4_4") (pintype "passive"))
      (node (ref "P1") (pin "5") (pinfunction "5_5") (pintype "passive"))
      (node (ref "P1") (pin "6") (pinfunction "6_6") (pintype "passive"))
      (node (ref "P1") (pin "7") (pinfunction "7_7") (pintype "passive"))
      (node (ref "P1") (pin "8") (pinfunction "8_8") (pintype "passive"))
      (node (ref "P1") (pin "9") (pinfunction "9_9") (pintype "passive"))
      (node (ref "Q1") (pin "2") (pinfunction "D_2") (pintype "passive"))
      (node (ref "Q2") (pin "2") (pinfunction "D_2") (pintype "passive"))
      (node (ref "Q3") (pin "2") (pinfunction "D_2") (pintype "passive"))
      (node (ref "S1") (pin "1") (pinfunction "+_1") (pintype "passive"))
    )
    (net (code "43") (name "GND") (class "Default")
      (node (ref "C1") (pin "1") (pinfunction "1_1") (pintype "passive"))
      (node (ref "C16") (pin "1") (pinfunction "1_1") (pintype "passive"))
      (node (ref "C17") (pin "1") (pinfunction "1_1") (pintype "passive"))
      (node (ref "C18") (pin "1") (pinfunction "1_1") (pintype "passive"))
      (node (ref "C2") (pin "1") (pinfunction "1_1") (pintype "passive"))
      (node (ref "C28") (pin "1") (pinfunction "1_1") (pintype "passive"))
      (node (ref "C29") (pin "1") (pinfunction "1_1") (pintype "passive"))
      (node (ref "C32") (pin "1") (pinfunction "1_1") (pintype "passive"))
      (node (ref "C33") (pin "1") (pinfunction "1_1") (pintype "passive"))
      (node (ref "C34") (pin "1") (pinfunction "1_1") (pintype "passive"))
      (node (ref "IC1") (pin "4") (pinfunction "GND_4") (pintype "passive"))
      (node (ref "IC2") (pin "4") (pinfunction "GND_4") (pintype "passive"))
      (node (ref "IC3") (pin "4") (pinfunction "GND_4") (pintype "passive"))
      (node (ref "NTC1") (pin "2") (pinfunction "2_2") (pintype "passive"))
      (node (ref "NTC2") (pin "2") (pinfunction "2_2") (pintype "passive"))
      (node (ref "P1") (pin "12") (pinfunction "12_12") (pintype "passive"))
      (node (ref "R1") (pin "2") (pinfunction "2_2") (pintype "passive"))
      (node (ref "R2") (pin "1") (pinfunction "1_1") (pintype "passive"))
      (node (ref "R3") (pin "2") (pinfunction "2_2") (pintype "passive"))
      (node (ref "R4") (pin "1") (pinfunction "1_1") (pintype "passive"))
      (node (ref "R53") (pin "2") (pinfunction "2_2") (pintype "passive"))
      (node (ref "R54") (pin "2") (pinfunction "2_2") (pintype "passive"))
      (node (ref "R55") (pin "2") (pinfunction "2_2") (pintype "passive"))
      (node (ref "U1") (pin "6") (pinfunction "COM_6") (pintype "passive"))
    )
    (net (code "44") (name "MA") (class "Default")
      (node (ref "CON1") (pin "1") (pinfunction "1_1") (pintype "passive"))
      (node (ref "CON2") (pin "3") (pinfunction "3_3") (pintype "passive"))
      (node (ref "CON3") (pin "1") (pinfunction "1_1") (pintype "passive"))
      (node (ref "CON4") (pin "1") (pinfunction "1_1") (pintype "passive"))
      (node (ref "CON5") (pin "1") (pinfunction "1_1") (pintype "passive"))
      (node (ref "IC1") (pin "2") (pinfunction "IN+_2") (pintype "passive"))
      (node (ref "R20") (pin "2") (pinfunction "2_2") (pintype "passive"))
      (node (ref "R48") (pin "1") (pinfunction "1_1") (pintype "passive"))
      (node (ref "pad8") (pin "1") (pinfunction "1_1") (pintype "passive"))
    )
    (net (code "45") (name "MB") (class "Default")
      (node (ref "CON1") (pin "2") (pinfunction "2_2") (pintype "passive"))
      (node (ref "CON2") (pin "2") (pinfunction "2_2") (pintype "passive"))
      (node (ref "CON3") (pin "2") (pinfunction "2_2") (pintype "passive"))
      (node (ref "CON4") (pin "2") (pinfunction "2_2") (pintype "passive"))
      (node (ref "CON5") (pin "2") (pinfunction "2_2") (pintype "passive"))
      (node (ref "IC2") (pin "2") (pinfunction "IN+_2") (pintype "passive"))
      (node (ref "R21") (pin "2") (pinfunction "2_2") (pintype "passive"))
      (node (ref "R49") (pin "1") (pinfunction "1_1") (pintype "passive"))
      (node (ref "pad9") (pin "1") (pinfunction "1_1") (pintype "passive"))
    )
    (net (code "46") (name "MC") (class "Default")
      (node (ref "CON1") (pin "3") (pinfunction "3_3") (pintype "passive"))
      (node (ref "CON2") (pin "1") (pinfunction "1_1") (pintype "passive"))
      (node (ref "CON3") (pin "3") (pinfunction "3_3") (pintype "passive"))
      (node (ref "CON4") (pin "3") (pinfunction "3_3") (pintype "passive"))
      (node (ref "CON5") (pin "3") (pinfunction "3_3") (pintype "passive"))
      (node (ref "IC3") (pin "2") (pinfunction "IN+_2") (pintype "passive"))
      (node (ref "R22") (pin "2") (pinfunction "2_2") (pintype "passive"))
      (node (ref "R50") (pin "1") (pinfunction "1_1") (pintype "passive"))
      (node (ref "pad10") (pin "1") (pinfunction "1_1") (pintype "passive"))
    )
    (net (code "47") (name "Net-(IC4-IN+)") (class "Default")
      (node (ref "C19") (pin "2") (pinfunction "2_2") (pintype "passive"))
      (node (ref "IC4") (pin "1") (pinfunction "IN+_1") (pintype "passive"))
      (node (ref "R5") (pin "2") (pinfunction "2_2") (pintype "passive"))
      (node (ref "R7") (pin "2") (pinfunction "2_2") (pintype "passive"))
      (node (ref "pad1") (pin "1") (pinfunction "1_1") (pintype "passive"))
    )
    (net (code "48") (name "Net-(IC5A-IN1+)") (class "Default")
      (node (ref "IC5") (pin "3") (pinfunction "IN1+_3") (pintype "passive"))
      (node (ref "R18") (pin "2") (pinfunction "2_2") (pintype "passive"))
      (node (ref "R19") (pin "2") (pinfunction "2_2") (pintype "passive"))
    )
    (net (code "49") (name "Net-(IC5A-IN1-)") (class "Default")
      (node (ref "IC5") (pin "2") (pinfunction "IN1-_2") (pintype "passive"))
      (node (ref "R16") (pin "2") (pinfunction "2_2") (pintype "passive"))
      (node (ref "R9") (pin "1") (pinfunction "1_1") (pintype "passive"))
    )
    (net (code "50") (name "Net-(IC5A-OUT1)") (class "Default")
      (node (ref "IC5") (pin "1") (pinfunction "OUT1_1") (pintype "passive"))
      (node (ref "R17") (pin "1") (pinfunction "1_1") (pintype "passive"))
      (node (ref "R9") (pin "2") (pinfunction "2_2") (pintype "passive"))
    )
    (net (code "51") (name "Net-(IC5B-IN2+)") (class "Default")
      (node (ref "IC5") (pin "5") (pinfunction "IN2+_5") (pintype "passive"))
      (node (ref "R43") (pin "2") (pinfunction "2_2") (pintype "passive"))
      (node (ref "R44") (pin "2") (pinfunction "2_2") (pintype "passive"))
    )
    (net (code "52") (name "Net-(IC5B-IN2-)") (class "Default")
      (node (ref "IC5") (pin "6") (pinfunction "IN2-_6") (pintype "passive"))
      (node (ref "R39") (pin "1") (pinfunction "1_1") (pintype "passive"))
      (node (ref "R40") (pin "2") (pinfunction "2_2") (pintype "passive"))
    )
    (net (code "53") (name "Net-(IC5B-OUT2)") (class "Default")
      (node (ref "IC5") (pin "7") (pinfunction "OUT2_7") (pintype "passive"))
      (node (ref "R39") (pin "2") (pinfunction "2_2") (pintype "passive"))
      (node (ref "R41") (pin "1") (pinfunction "1_1") (pintype "passive"))
    )
    (net (code "54") (name "Net-(IC5C-IN3+)") (class "Default")
      (node (ref "IC5") (pin "10") (pinfunction "IN3+_10") (pintype "passive"))
      (node (ref "R51") (pin "2") (pinfunction "2_2") (pintype "passive"))
      (node (ref "R52") (pin "2") (pinfunction "2_2") (pintype "passive"))
    )
    (net (code "55") (name "Net-(IC5C-IN3-)") (class "Default")
      (node (ref "IC5") (pin "9") (pinfunction "IN3-_9") (pintype "passive"))
      (node (ref "R45") (pin "1") (pinfunction "1_1") (pintype "passive"))
      (node (ref "R46") (pin "2") (pinfunction "2_2") (pintype "passive"))
    )
    (net (code "56") (name "Net-(IC5C-OUT3)") (class "Default")
      (node (ref "IC5") (pin "8") (pinfunction "OUT3_8") (pintype "passive"))
      (node (ref "R45") (pin "2") (pinfunction "2_2") (pintype "passive"))
      (node (ref "R47") (pin "1") (pinfunction "1_1") (pintype "passive"))
    )
    (net (code "57") (name "Net-(IC5D-IN4+)") (class "Default")
      (node (ref "IC5") (pin "12") (pinfunction "IN4+_12") (pintype "passive"))
      (node (ref "R32") (pin "2") (pinfunction "2_2") (pintype "passive"))
      (node (ref "R35") (pin "2") (pinfunction "2_2") (pintype "passive"))
    )
    (net (code "58") (name "Net-(IC5D-IN4-)") (class "Default")
      (node (ref "IC5") (pin "13") (pinfunction "IN4-_13") (pintype "passive"))
      (node (ref "R23") (pin "1") (pinfunction "1_1") (pintype "passive"))
      (node (ref "R30") (pin "2") (pinfunction "2_2") (pintype "passive"))
    )
    (net (code "59") (name "Net-(IC5D-OUT4)") (class "Default")
      (node (ref "IC5") (pin "14") (pinfunction "OUT4_14") (pintype "passive"))
      (node (ref "R23") (pin "2") (pinfunction "2_2") (pintype "passive"))
      (node (ref "R31") (pin "1") (pinfunction "1_1") (pintype "passive"))
    )
    (net (code "60") (name "Net-(Q1-G)") (class "Default")
      (node (ref "C20") (pin "2") (pinfunction "2_2") (pintype "passive"))
      (node (ref "D4") (pin "1") (pintype "passive"))
      (node (ref "Q1") (pin "1") (pinfunction "G_1") (pintype "passive"))
      (node (ref "R10") (pin "1") (pinfunction "1_1") (pintype "passive"))
      (node (ref "R13") (pin "1") (pinfunction "1_1") (pintype "passive"))
      (node (ref "pad2") (pin "1") (pinfunction "1_1") (pintype "passive"))
    )
    (net (code "61") (name "Net-(Q2-G)") (class "Default")
      (node (ref "C21") (pin "2") (pinfunction "2_2") (pintype "passive"))
      (node (ref "D5") (pin "1") (pintype "passive"))
      (node (ref "Q2") (pin "1") (pinfunction "G_1") (pintype "passive"))
      (node (ref "R11") (pin "1") (pinfunction "1_1") (pintype "passive"))
      (node (ref "R14") (pin "1") (pinfunction "1_1") (pintype "passive"))
      (node (ref "pad3") (pin "1") (pinfunction "1_1") (pintype "passive"))
    )
    (net (code "62") (name "Net-(Q3-G)") (class "Default")
      (node (ref "C22") (pin "2") (pinfunction "2_2") (pintype "passive"))
      (node (ref "D6") (pin "1") (pintype "passive"))
      (node (ref "Q3") (pin "1") (pinfunction "G_1") (pintype "passive"))
      (node (ref "R12") (pin "1") (pinfunction "1_1") (pintype "passive"))
      (node (ref "R15") (pin "1") (pinfunction "1_1") (pintype "passive"))
      (node (ref "pad4") (pin "1") (pinfunction "1_1") (pintype "passive"))
    )
    (net (code "63") (name "Net-(Q4-G)") (class "Default")
      (node (ref "C24") (pin "2") (pinfunction "2_2") (pintype "passive"))
      (node (ref "D7") (pin "1") (pintype "passive"))
      (node (ref "Q4") (pin "1") (pinfunction "G_1") (pintype "passive"))
      (node (ref "R24") (pin "1") (pinfunction "1_1") (pintype "passive"))
      (node (ref "R27") (pin "1") (pinfunction "1_1") (pintype "passive"))
      (node (ref "pad11") (pin "1") (pinfunction "1_1") (pintype "passive"))
    )
    (net (code "64") (name "Net-(Q5-G)") (class "Default")
      (node (ref "C25") (pin "2") (pinfunction "2_2") (pintype "passive"))
      (node (ref "D8") (pin "1") (pintype "passive"))
      (node (ref "Q5") (pin "1") (pinfunction "G_1") (pintype "passive"))
      (node (ref "R25") (pin "1") (pinfunction "1_1") (pintype "passive"))
      (node (ref "R28") (pin "1") (pinfunction "1_1") (pintype "passive"))
      (node (ref "pad12") (pin "1") (pinfunction "1_1") (pintype "passive"))
    )
    (net (code "65") (name "Net-(Q6-G)") (class "Default")
      (node (ref "C26") (pin "2") (pinfunction "2_2") (pintype "passive"))
      (node (ref "D9") (pin "1") (pintype "passive"))
      (node (ref "Q6") (pin "1") (pinfunction "G_1") (pintype "passive"))
      (node (ref "R26") (pin "1") (pinfunction "1_1") (pintype "passive"))
      (node (ref "R29") (pin "1") (pinfunction "1_1") (pintype "passive"))
      (node (ref "pad13") (pin "1") (pinfunction "1_1") (pintype "passive"))
    )
    (net (code "66") (name "Net-(R6-Pad2)") (class "Default")
      (node (ref "R6") (pin "2") (pinfunction "2_2") (pintype "passive"))
      (node (ref "R7") (pin "1") (pinfunction "1_1") (pintype "passive"))
      (node (ref "R8") (pin "1") (pinfunction "1_1") (pintype "passive"))
    )
    (net (code "67") (name "PGND") (class "Default")
      (node (ref "C10") (pin "1") (pinfunction "1_1") (pintype "passive"))
      (node (ref "C11") (pin "1") (pinfunction "1_1") (pintype "passive"))
      (node (ref "C12") (pin "1") (pinfunction "1_1") (pintype "passive"))
      (node (ref "C13") (pin "1") (pinfunction "1_1") (pintype "passive"))
      (node (ref "C14") (pin "1") (pinfunction "1_1") (pintype "passive"))
      (node (ref "C15") (pin "1") (pinfunction "1_1") (pintype "passive"))
      (node (ref "C6") (pin "1") (pinfunction "1_1") (pintype "passive"))
      (node (ref "C7") (pin "1") (pinfunction "1_1") (pintype "passive"))
      (node (ref "C8") (pin "1") (pinfunction "1_1") (pintype "passive"))
      (node (ref "C9") (pin "1") (pinfunction "1_1") (pintype "passive"))
      (node (ref "CON1") (pin "0") (pinfunction "0_0") (pintype "passive"))
      (node (ref "P1") (pin "14") (pinfunction "14_14") (pintype "passive"))
      (node (ref "P1") (pin "15") (pinfunction "15_15") (pintype "passive"))
      (node (ref "P1") (pin "16") (pinfunction "16_16") (pintype "passive"))
      (node (ref "P1") (pin "17") (pinfunction "17_17") (pintype "passive"))
      (node (ref "P1") (pin "18") (pinfunction "18_18") (pintype "passive"))
      (node (ref "P1") (pin "19") (pinfunction "19_19") (pintype "passive"))
      (node (ref "P1") (pin "20") (pinfunction "20_20") (pintype "passive"))
      (node (ref "P1") (pin "21") (pinfunction "21_21") (pintype "passive"))
      (node (ref "P1") (pin "22") (pinfunction "22_22") (pintype "passive"))
      (node (ref "P1") (pin "23") (pinfunction "23_23") (pintype "passive"))
      (node (ref "P1") (pin "24") (pinfunction "24_24") (pintype "passive"))
      (node (ref "R1") (pin "1") (pinfunction "1_1") (pintype "passive"))
      (node (ref "R3") (pin "1") (pinfunction "1_1") (pintype "passive"))
      (node (ref "R30") (pin "1") (pinfunction "1_1") (pintype "passive"))
      (node (ref "R42") (pin "1") (pinfunction "1_1") (pintype "passive"))
      (node (ref "S1") (pin "2") (pinfunction "-_2") (pintype "passive"))
      (node (ref "S1") (pin "3") (pinfunction "3_3") (pintype "passive"))
      (node (ref "S1") (pin "4") (pinfunction "4_4") (pintype "passive"))
    )
    (net (code "68") (name "unconnected-(IC1-NC-Pad1)") (class "Default")
      (node (ref "IC1") (pin "1") (pinfunction "NC_1") (pintype "passive+no_connect"))
    )
    (net (code "69") (name "unconnected-(IC2-NC-Pad1)") (class "Default")
      (node (ref "IC2") (pin "1") (pinfunction "NC_1") (pintype "passive+no_connect"))
    )
    (net (code "70") (name "unconnected-(IC3-NC-Pad1)") (class "Default")
      (node (ref "IC3") (pin "1") (pinfunction "NC_1") (pintype "passive+no_connect"))
    )
    (net (code "71") (name "unconnected-(P2-Pad23)") (class "Default")
      (node (ref "P2") (pin "23") (pinfunction "23_23") (pintype "passive+no_connect"))
    )
    (net (code "72") (name "unconnected-(U1-EP-Pad25)") (class "Default")
      (node (ref "U1") (pin "25") (pinfunction "EP_25") (pintype "passive"))
    )
    (net (code "73") (name "unconnected-(U1-NC-Pad5)") (class "Default")
      (node (ref "U1") (pin "5") (pinfunction "NC_5") (pintype "passive+no_connect"))
    )
    (net (code "74") (name "unconnected-(U1-NC-Pad7)") (class "Default")
      (node (ref "U1") (pin "7") (pinfunction "NC_7") (pintype "passive+no_connect"))
    )
    (net (code "75") (name "unconnected-(U1-NC-Pad8)") (class "Default")
      (node (ref "U1") (pin "8") (pinfunction "NC_8") (pintype "passive+no_connect"))
    )
    (net (code "76") (name "unconnected-(U1-NC-Pad21)") (class "Default")
      (node (ref "U1") (pin "21") (pinfunction "NC_21") (pintype "passive+no_connect"))
    )
  )
)
